# sensor_board.net
KiCad netlist of a schematic drawn in EAGLE
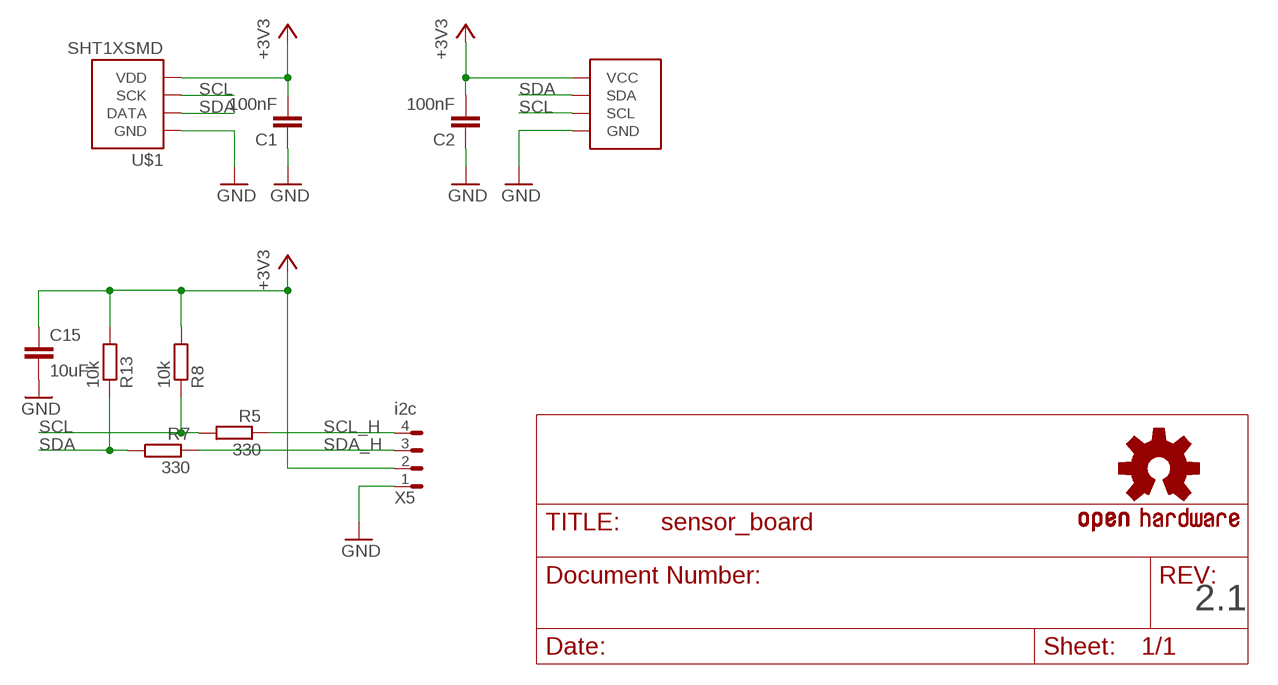
[diagram p0: schematic, sheet 1]

(export (version "E")
  (design (tool "Eeschema 10.0.6"))
  (components
    (comp (ref "C1")
      (value "100nF")
      (footprint "eagle-import:C0805")
      (libsource (lib "eagle-import") (part "C-EUC0805"))
    )
    (comp (ref "C2")
      (value "100nF")
      (footprint "eagle-import:C0805")
      (libsource (lib "eagle-import") (part "C-EUC0805"))
    )
    (comp (ref "C15")
      (value "10uF")
      (footprint "eagle-import:C1206")
      (libsource (lib "eagle-import") (part "C-EUC1206"))
    )
    (comp (ref "R5")
      (value "330")
      (footprint "eagle-import:R0805W")
      (libsource (lib "eagle-import") (part "R-EU_R0805W"))
    )
    (comp (ref "R7")
      (value "330")
      (footprint "eagle-import:R0805W")
      (libsource (lib "eagle-import") (part "R-EU_R0805W"))
    )
    (comp (ref "R8")
      (value "10k")
      (footprint "eagle-import:R0805W")
      (libsource (lib "eagle-import") (part "R-EU_R0805W"))
    )
    (comp (ref "R13")
      (value "10k")
      (footprint "eagle-import:R0805W")
      (libsource (lib "eagle-import") (part "R-EU_R0805W"))
    )
    (comp (ref "U$1")
      (value "SHT1XSMD")
      (footprint "eagle-import:SHT1X")
      (libsource (lib "eagle-import") (part "SHT1XSMD"))
    )
    (comp (ref "U$2")
      (value "HONEYWELL_HSC")
      (footprint "eagle-import:HONEYWELL_8_SMT")
      (libsource (lib "eagle-import") (part "HONEYWELL_HSC"))
    )
    (comp (ref "U$7")
      (value "OSHW-LOGOM")
      (footprint "eagle-import:OSHW-LOGO-M")
      (libsource (lib "eagle-import") (part "OSHW-LOGOM"))
    )
    (comp (ref "X5")
      (value "i2c")
      (footprint "eagle-import:0530480401")
      (libsource (lib "eagle-import") (part "MOLEX_4HORIZONTAL"))
    )
  )
  (nets
    (net (code "1") (name "+3V3") (class "Default")
      (node (ref "C1") (pin "2") (pinfunction "2_2") (pintype "passive"))
      (node (ref "C15") (pin "1") (pinfunction "1_1") (pintype "passive"))
      (node (ref "C2") (pin "2") (pinfunction "2_2") (pintype "passive"))
      (node (ref "R13") (pin "2") (pinfunction "2_2") (pintype "passive"))
      (node (ref "R8") (pin "2") (pinfunction "2_2") (pintype "passive"))
      (node (ref "U$1") (pin "4") (pinfunction "VDD_4") (pintype "power_in"))
      (node (ref "U$2") (pin "P$2") (pinfunction "VCC_P$2") (pintype "power_in"))
      (node (ref "X5") (pin "2") (pinfunction "3_2") (pintype "passive"))
    )
    (net (code "2") (name "/SCL") (class "Default")
      (node (ref "R5") (pin "2") (pinfunction "2_2") (pintype "passive"))
      (node (ref "R8") (pin "1") (pinfunction "1_1") (pintype "passive"))
      (node (ref "U$1") (pin "3") (pinfunction "SCK_3") (pintype "input"))
      (node (ref "U$2") (pin "P$4") (pinfunction "SCL_P$4") (pintype "bidirectional"))
    )
    (net (code "3") (name "/SCL_H") (class "Default")
      (node (ref "R5") (pin "1") (pinfunction "1_1") (pintype "passive"))
      (node (ref "X5") (pin "4") (pinfunction "1_4") (pintype "passive"))
    )
    (net (code "4") (name "/SDA") (class "Default")
      (node (ref "R13") (pin "1") (pinfunction "1_1") (pintype "passive"))
      (node (ref "R7") (pin "2") (pinfunction "2_2") (pintype "passive"))
      (node (ref "U$1") (pin "2") (pinfunction "DATA_2") (pintype "bidirectional"))
      (node (ref "U$2") (pin "P$3") (pinfunction "SDA_P$3") (pintype "bidirectional"))
    )
    (net (code "5") (name "/SDA_H") (class "Default")
      (node (ref "R7") (pin "1") (pinfunction "1_1") (pintype "passive"))
      (node (ref "X5") (pin "3") (pinfunction "2_3") (pintype "passive"))
    )
    (net (code "6") (name "GND") (class "Default")
      (node (ref "C1") (pin "1") (pinfunction "1_1") (pintype "passive"))
      (node (ref "C15") (pin "2") (pinfunction "2_2") (pintype "passive"))
      (node (ref "C2") (pin "1") (pinfunction "1_1") (pintype "passive"))
      (node (ref "U$1") (pin "1") (pinfunction "GND_1") (pintype "power_in"))
      (node (ref "U$2") (pin "P$1") (pinfunction "GND_P$1") (pintype "power_in"))
      (node (ref "X5") (pin "1") (pinfunction "4_1") (pintype "passive"))
    )
  )
)
